# RTC.net
KiCad netlist of a schematic drawn in Altium Designer
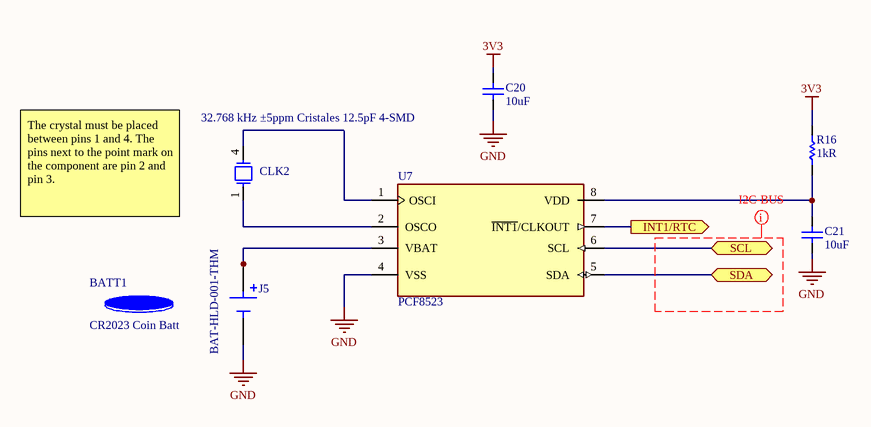
[diagram p0: RTC.SchDoc]

(export (version "E")
  (design (tool "Eeschema 10.0.6"))
  (components
    (comp (ref "BATT1")
      (value "CR2023 Coin Batt")
      (footprint "CR2032 BATT")
      (description "CR2032 Series Ø 20 mm 3V 225mAh Non-Rechargeable Lithium Coin Cell Battery")
      (fields (field (name "MANUFACTURER") "Panasonic BSG") (field (name "VOLTAGE") "3V"))
      (libsource (lib "stratos") (part "CR2023 Coin Batt"))
    )
    (comp (ref "C20")
      (value "10uF")
      (footprint "Cap 0805 (2012 Metric)")
      (description "CAP CER 10UF 10V X5R 0805")
      (fields
        (field (name "MANUFACTURER") "KEMET")
        (field (name "MANUFACTURER PART NUMBER") "C0805C106K8PACTU")
      )
      (libsource (lib "Daniel_Integrated_Library") (part "Capacitor"))
    )
    (comp (ref "C21")
      (value "10uF")
      (footprint "Cap 0805 (2012 Metric)")
      (description "CAP CER 10UF 10V X5R 0805")
      (fields
        (field (name "MANUFACTURER") "KEMET")
        (field (name "MANUFACTURER PART NUMBER") "C0805C106K8PACTU")
      )
      (libsource (lib "Daniel_Integrated_Library") (part "Capacitor"))
    )
    (comp (ref "CLK2")
      (value "32.768 kHz ±5ppm Cristales 12.5pF 4-SMD")
      (footprint "Crystal32768")
      (description "8.0x3.8 - 32.768KHz Quartz Xtal / Plastic, +/-5ppm @25C, 12.5pF")
      (fields
        (field (name "MANUFACTURER") "QST")
        (field (name "MANUFACTURER PART NUMBER") "QT2M-32.768KHZF-T")
      )
      (libsource (lib "K2K_LoRaWAN") (part "Crystal32768"))
    )
    (comp (ref "J5")
      (value "BAT-HLD-001-THM")
      (footprint "BAT-HLD-001-THM")
      (description "BATTERY RETAINER COIN PC PIN")
      (fields (field (name "MANUFACTURER") "Linx"))
      (libsource (lib "stratos") (part "BAT-HLD-001-THM"))
    )
    (comp (ref "R16")
      (value "1kR")
      (footprint "Res 0805 (2012 Metric)")
      (description "RES 1K OHM 1% 1/4W 0805")
      (fields
        (field (name "MANUFACTURER") "Stackpole Electronics")
        (field (name "MANUFACTURER PART NUMBER") "RNCP0805FTD1K00")
      )
      (libsource (lib "Daniel_Integrated_Library") (part "Resistor"))
    )
    (comp (ref "U7")
      (value "PCF8523")
      (footprint "PCF8523")
      (description "IC RTC CLK/CALENDAR I2C 8-SOIC")
      (fields
        (field (name "MANUFACTURER") "NXP Semiconductors")
        (field (name "MANUFACTURER PART NUMBER") "PCF8523T/1,118")
      )
      (libsource (lib "stratos") (part "PCF8523"))
    )
  )
  (nets
    (net (code "1") (name "/INT1{slash}RTC") (class "Default")
      (node (ref "U7") (pin "7") (pinfunction "~{INT1}/CLKOUT_7") (pintype "output"))
    )
    (net (code "2") (name "/SCL") (class "Default")
      (node (ref "U7") (pin "6") (pinfunction "SCL_6") (pintype "input"))
    )
    (net (code "3") (name "/SDA") (class "Default")
      (node (ref "U7") (pin "5") (pinfunction "SDA_5") (pintype "bidirectional"))
    )
    (net (code "4") (name "3V3") (class "Default")
      (node (ref "C20") (pin "1") (pinfunction "1_1") (pintype "passive"))
      (node (ref "R16") (pin "1") (pinfunction "1_1") (pintype "passive"))
    )
    (net (code "5") (name "GND") (class "Default")
      (node (ref "C20") (pin "2") (pinfunction "2_2") (pintype "passive"))
      (node (ref "C21") (pin "2") (pinfunction "2_2") (pintype "passive"))
      (node (ref "J5") (pin "N") (pinfunction "N_N") (pintype "passive"))
      (node (ref "U7") (pin "4") (pinfunction "VSS_4") (pintype "power_in"))
    )
    (net (code "6") (name "Net-(U7-OSCI)") (class "Default")
      (node (ref "CLK2") (pin "4") (pinfunction "4_4") (pintype "passive"))
      (node (ref "U7") (pin "1") (pinfunction "OSCI_1") (pintype "passive"))
    )
    (net (code "7") (name "Net-(U7-OSCO)") (class "Default")
      (node (ref "CLK2") (pin "1") (pinfunction "1_1") (pintype "passive"))
      (node (ref "U7") (pin "2") (pinfunction "OSCO_2") (pintype "passive"))
    )
    (net (code "8") (name "Net-(U7-VBAT)") (class "Default")
      (node (ref "J5") (pin "P1") (pinfunction "P_P1") (pintype "passive"))
      (node (ref "J5") (pin "P2") (pinfunction "P_P2") (pintype "passive"))
      (node (ref "J5") (pin "P3") (pinfunction "P_P3") (pintype "passive"))
      (node (ref "J5") (pin "P4") (pinfunction "P_P4") (pintype "passive"))
      (node (ref "U7") (pin "3") (pinfunction "VBAT_3") (pintype "power_in"))
    )
    (net (code "9") (name "Net-(U7-VDD)") (class "Default")
      (node (ref "C21") (pin "1") (pinfunction "1_1") (pintype "passive"))
      (node (ref "R16") (pin "2") (pinfunction "2_2") (pintype "passive"))
      (node (ref "U7") (pin "8") (pinfunction "VDD_8") (pintype "power_in"))
    )
  )
)
